# Flatsat_Connectors.net
KiCad netlist of a schematic drawn in Altium Designer
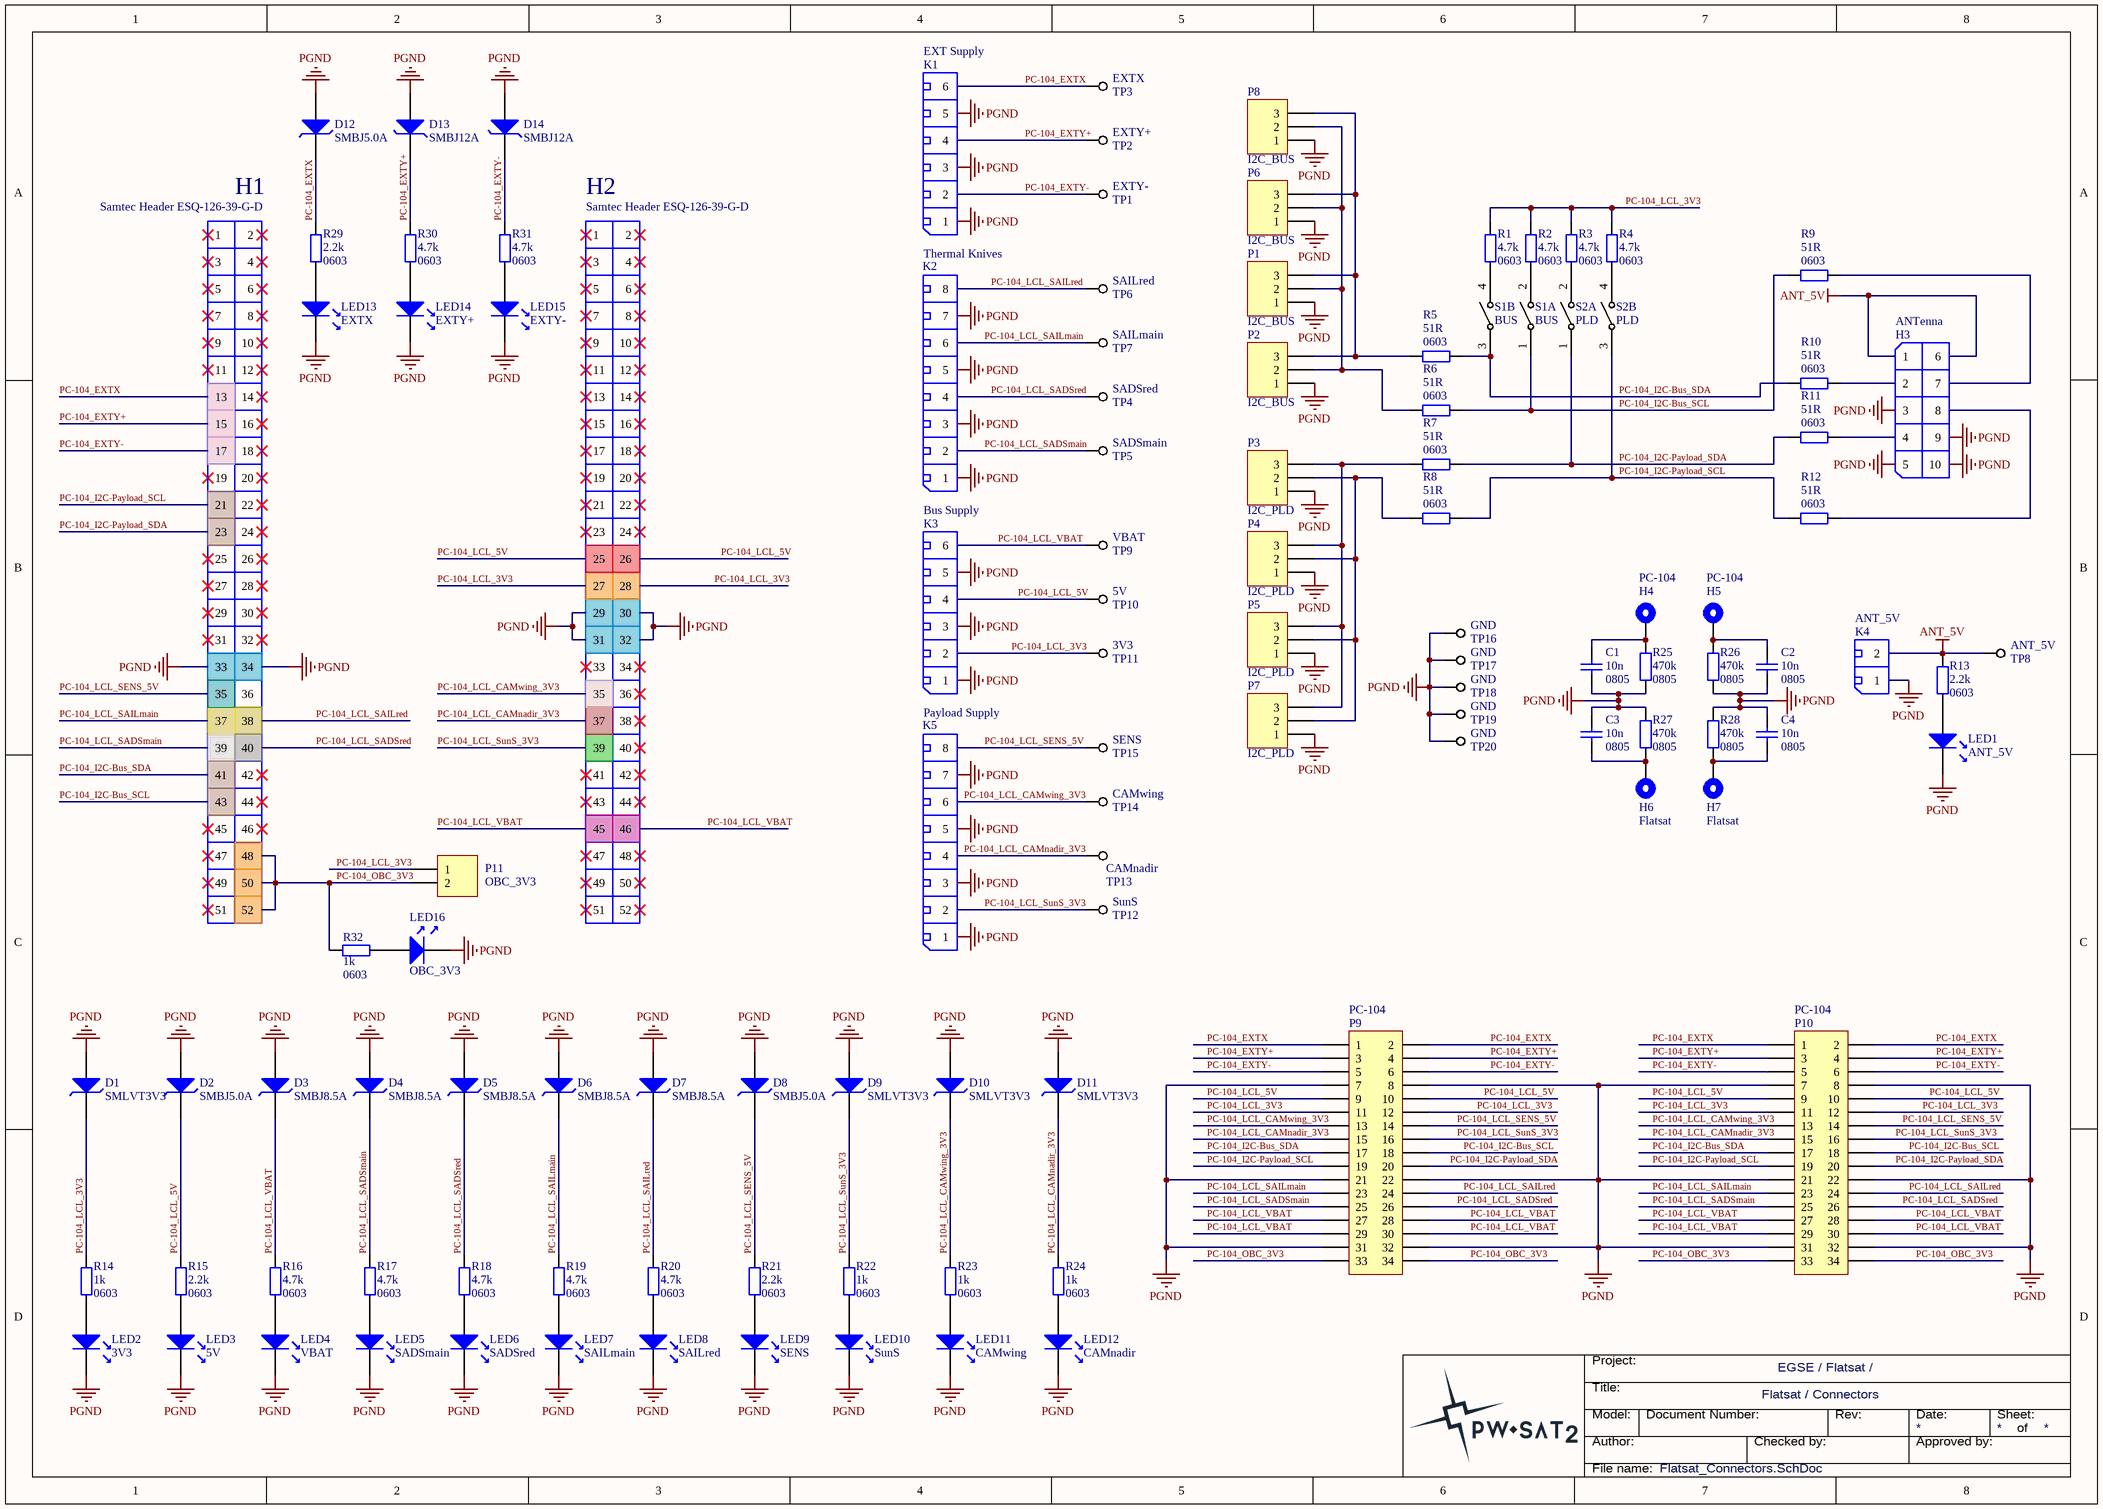
[diagram p0: Flatsat_Connectors.SchDoc]

(export (version "E")
  (design (tool "Eeschema 10.0.6"))
  (components
    (comp (ref "C1")
      (value "10n")
      (footprint "SMD_Capacitor_0805")
      (description "Cap")
      (fields (field (name "PACKAGE") "0805"))
      (libsource (lib "capacitors") (part "Cap"))
    )
    (comp (ref "C2")
      (value "10n")
      (footprint "SMD_Capacitor_0805")
      (description "Cap")
      (fields (field (name "PACKAGE") "0805"))
      (libsource (lib "capacitors") (part "Cap"))
    )
    (comp (ref "C3")
      (value "10n")
      (footprint "SMD_Capacitor_0805")
      (description "Cap")
      (fields (field (name "PACKAGE") "0805"))
      (libsource (lib "capacitors") (part "Cap"))
    )
    (comp (ref "C4")
      (value "10n")
      (footprint "SMD_Capacitor_0805")
      (description "Cap")
      (fields (field (name "PACKAGE") "0805"))
      (libsource (lib "capacitors") (part "Cap"))
    )
    (comp (ref "D1")
      (value "SMLVT3V3")
      (footprint "DO-214AA")
      (description "Low voltage Transil 3.3V")
      (fields (field (name "MANUFACTURER") "STMicroelectronics"))
      (libsource (lib "diodes") (part "SMLVT3V3"))
    )
    (comp (ref "D2")
      (value "SMBJ5.0A")
      (footprint "DO-214AA")
      (description "Transil 5V")
      (fields (field (name "MANUFACTURER") "STMicroelectronics"))
      (libsource (lib "diodes") (part "SMBJ5.0A"))
    )
    (comp (ref "D3")
      (value "SMBJ8.5A")
      (footprint "DO-214AA")
      (description "Transient Voltage Suppression Diodes 8.5V")
      (fields (field (name "MANUFACTURER") "Littelfuse"))
      (libsource (lib "diodes") (part "SMBJ8.5A"))
    )
    (comp (ref "D4")
      (value "SMBJ8.5A")
      (footprint "DO-214AA")
      (description "Transient Voltage Suppression Diodes 8.5V")
      (fields (field (name "MANUFACTURER") "Littelfuse"))
      (libsource (lib "diodes") (part "SMBJ8.5A"))
    )
    (comp (ref "D5")
      (value "SMBJ8.5A")
      (footprint "DO-214AA")
      (description "Transient Voltage Suppression Diodes 8.5V")
      (fields (field (name "MANUFACTURER") "Littelfuse"))
      (libsource (lib "diodes") (part "SMBJ8.5A"))
    )
    (comp (ref "D6")
      (value "SMBJ8.5A")
      (footprint "DO-214AA")
      (description "Transient Voltage Suppression Diodes 8.5V")
      (fields (field (name "MANUFACTURER") "Littelfuse"))
      (libsource (lib "diodes") (part "SMBJ8.5A"))
    )
    (comp (ref "D7")
      (value "SMBJ8.5A")
      (footprint "DO-214AA")
      (description "Transient Voltage Suppression Diodes 8.5V")
      (fields (field (name "MANUFACTURER") "Littelfuse"))
      (libsource (lib "diodes") (part "SMBJ8.5A"))
    )
    (comp (ref "D8")
      (value "SMBJ5.0A")
      (footprint "DO-214AA")
      (description "Transil 5V")
      (fields (field (name "MANUFACTURER") "STMicroelectronics"))
      (libsource (lib "diodes") (part "SMBJ5.0A"))
    )
    (comp (ref "D9")
      (value "SMLVT3V3")
      (footprint "DO-214AA")
      (description "Low voltage Transil 3.3V")
      (fields (field (name "MANUFACTURER") "STMicroelectronics"))
      (libsource (lib "diodes") (part "SMLVT3V3"))
    )
    (comp (ref "D10")
      (value "SMLVT3V3")
      (footprint "DO-214AA")
      (description "Low voltage Transil 3.3V")
      (fields (field (name "MANUFACTURER") "STMicroelectronics"))
      (libsource (lib "diodes") (part "SMLVT3V3"))
    )
    (comp (ref "D11")
      (value "SMLVT3V3")
      (footprint "DO-214AA")
      (description "Low voltage Transil 3.3V")
      (fields (field (name "MANUFACTURER") "STMicroelectronics"))
      (libsource (lib "diodes") (part "SMLVT3V3"))
    )
    (comp (ref "D12")
      (value "SMBJ5.0A")
      (footprint "DO-214AA")
      (description "Transil 5V")
      (fields (field (name "MANUFACTURER") "STMicroelectronics"))
      (libsource (lib "diodes") (part "SMBJ5.0A"))
    )
    (comp (ref "D13")
      (value "SMBJ12A")
      (footprint "DO-214AA")
      (description "Transil 12V")
      (fields (field (name "MANUFACTURER") "Littelfuse"))
      (libsource (lib "diodes") (part "SMBJ12A"))
    )
    (comp (ref "D14")
      (value "SMBJ12A")
      (footprint "DO-214AA")
      (description "Transil 12V")
      (fields (field (name "MANUFACTURER") "Littelfuse"))
      (libsource (lib "diodes") (part "SMBJ12A"))
    )
    (comp (ref "H1")
      (value "Samtec Header ESQ-126-39-G-D")
      (footprint "Samtec_ESQ-126-39-G-D")
      (description "Samtec ESQ Series Header , 2.54mm pitch, 2x26pin. PC-104 Stack Connector.")
      (libsource (lib "connectors_printed-circuit-board") (part "Samtec_ESQ-126-xx-x-D"))
    )
    (comp (ref "H2")
      (value "Samtec Header ESQ-126-39-G-D")
      (footprint "Samtec_ESQ-126-39-G-D")
      (description "Samtec ESQ Series Header , 2.54mm pitch, 2x26pin. PC-104 Stack Connector.")
      (libsource (lib "connectors_printed-circuit-board") (part "Samtec_ESQ-126-xx-x-D"))
    )
    (comp (ref "H3")
      (value "ANTenna")
      (footprint "Harwin_Datamate_L-Tek_M80-8671005")
      (description "Harwin DataMate L-Tek, 2mm pitch, 2x5pin.")
      (libsource (lib "connectors_printed-circuit-board") (part "Harwin_Datamate_L-Tek_2x5pin"))
    )
    (comp (ref "H4")
      (value "PC-104")
      (footprint "PC-104_PcbMntHole_M3")
      (description "PCB Mounting Hole")
      (libsource (lib "connectors_printed-circuit-board") (part "MntHole"))
    )
    (comp (ref "H5")
      (value "PC-104")
      (footprint "PC-104_PcbMntHole_M3")
      (description "PCB Mounting Hole")
      (libsource (lib "connectors_printed-circuit-board") (part "MntHole"))
    )
    (comp (ref "H6")
      (value "Flatsat")
      (footprint "PC-104_PcbMntHole_M3")
      (description "PCB Mounting Hole")
      (libsource (lib "connectors_printed-circuit-board") (part "MntHole"))
    )
    (comp (ref "H7")
      (value "Flatsat")
      (footprint "PC-104_PcbMntHole_M3")
      (description "PCB Mounting Hole")
      (libsource (lib "connectors_printed-circuit-board") (part "MntHole"))
    )
    (comp (ref "K1")
      (value "EXT Supply")
      (footprint "TerminalBlock_Spring_2.54_6-R")
      (description "Terminal block with spring, 6-pin, 2.54mm pitch, right angle.")
      (fields (field (name "PROVIDERPARTNUMBER") "TB-2.5-PD-xx") (field (name "PROVIDER") "TME.eu"))
      (libsource (lib "connectors_printed-circuit-board") (part "TerminalBlock_Spring_2.54_6-R"))
    )
    (comp (ref "K2")
      (value "Thermal Knives")
      (footprint "TerminalBlock_Spring_2.54_8-R")
      (description "Terminal block with spring, 8-pin, 2.54mm pitch, right angle.")
      (fields (field (name "PROVIDERPARTNUMBER") "TB-2.5-PD-xx") (field (name "PROVIDER") "TME.eu"))
      (libsource (lib "connectors_printed-circuit-board") (part "TerminalBlock_Spring_2.54_8-R"))
    )
    (comp (ref "K3")
      (value "Bus Supply")
      (footprint "TerminalBlock_Spring_2.54_6-R")
      (description "Terminal block with spring, 6-pin, 2.54mm pitch, right angle.")
      (fields (field (name "PROVIDERPARTNUMBER") "TB-2.5-PD-xx") (field (name "PROVIDER") "TME.eu"))
      (libsource (lib "connectors_printed-circuit-board") (part "TerminalBlock_Spring_2.54_6-R"))
    )
    (comp (ref "K4")
      (value "ANT_5V")
      (footprint "TerminalBlock_Spring_2.54_2-R")
      (description "Terminal block with spring, 2-pin, 2.54mm pitch, right angle.")
      (fields (field (name "PROVIDERPARTNUMBER") "TB-2.5-PD-xx") (field (name "PROVIDER") "TME.eu"))
      (libsource (lib "connectors_printed-circuit-board") (part "TerminalBlock_Spring_2.54_2-R"))
    )
    (comp (ref "K5")
      (value "Payload Supply")
      (footprint "TerminalBlock_Spring_2.54_8-R")
      (description "Terminal block with spring, 8-pin, 2.54mm pitch, right angle.")
      (fields (field (name "PROVIDERPARTNUMBER") "TB-2.5-PD-xx") (field (name "PROVIDER") "TME.eu"))
      (libsource (lib "connectors_printed-circuit-board") (part "TerminalBlock_Spring_2.54_8-R"))
    )
    (comp (ref "LED1")
      (value "ANT_5V")
      (footprint "SMD_LED_1206")
      (description "LED diode, SMD1206 package.")
      (libsource (lib "diodes") (part "LED-1206_RED"))
    )
    (comp (ref "LED2")
      (value "3V3")
      (footprint "SMD_LED_1206")
      (description "LED diode, SMD1206 package.")
      (libsource (lib "diodes") (part "LED-1206_RED"))
    )
    (comp (ref "LED3")
      (value "5V")
      (footprint "SMD_LED_1206")
      (description "LED diode, SMD1206 package.")
      (libsource (lib "diodes") (part "LED-1206_RED"))
    )
    (comp (ref "LED4")
      (value "VBAT")
      (footprint "SMD_LED_1206")
      (description "LED diode, SMD1206 package.")
      (libsource (lib "diodes") (part "LED-1206_RED"))
    )
    (comp (ref "LED5")
      (value "SADSmain")
      (footprint "SMD_LED_1206")
      (description "LED diode, SMD1206 package.")
      (libsource (lib "diodes") (part "LED-1206_RED"))
    )
    (comp (ref "LED6")
      (value "SADSred")
      (footprint "SMD_LED_1206")
      (description "LED diode, SMD1206 package.")
      (libsource (lib "diodes") (part "LED-1206_RED"))
    )
    (comp (ref "LED7")
      (value "SAILmain")
      (footprint "SMD_LED_1206")
      (description "LED diode, SMD1206 package.")
      (libsource (lib "diodes") (part "LED-1206_RED"))
    )
    (comp (ref "LED8")
      (value "SAILred")
      (footprint "SMD_LED_1206")
      (description "LED diode, SMD1206 package.")
      (libsource (lib "diodes") (part "LED-1206_RED"))
    )
    (comp (ref "LED9")
      (value "SENS")
      (footprint "SMD_LED_1206")
      (description "LED diode, SMD1206 package.")
      (libsource (lib "diodes") (part "LED-1206_RED"))
    )
    (comp (ref "LED10")
      (value "SunS")
      (footprint "SMD_LED_1206")
      (description "LED diode, SMD1206 package.")
      (libsource (lib "diodes") (part "LED-1206_RED"))
    )
    (comp (ref "LED11")
      (value "CAMwing")
      (footprint "SMD_LED_1206")
      (description "LED diode, SMD1206 package.")
      (libsource (lib "diodes") (part "LED-1206_RED"))
    )
    (comp (ref "LED12")
      (value "CAMnadir")
      (footprint "SMD_LED_1206")
      (description "LED diode, SMD1206 package.")
      (libsource (lib "diodes") (part "LED-1206_RED"))
    )
    (comp (ref "LED13")
      (value "EXTX")
      (footprint "SMD_LED_1206")
      (description "LED diode, SMD1206 package.")
      (libsource (lib "diodes") (part "LED-1206_RED"))
    )
    (comp (ref "LED14")
      (value "EXTY+")
      (footprint "SMD_LED_1206")
      (description "LED diode, SMD1206 package.")
      (libsource (lib "diodes") (part "LED-1206_RED"))
    )
    (comp (ref "LED15")
      (value "EXTY-")
      (footprint "SMD_LED_1206")
      (description "LED diode, SMD1206 package.")
      (libsource (lib "diodes") (part "LED-1206_RED"))
    )
    (comp (ref "LED16")
      (value "OBC_3V3")
      (footprint "SMD_LED_1206")
      (description "LED diode, SMD1206 package.")
      (libsource (lib "diodes") (part "LED-1206_RED"))
    )
    (comp (ref "P1")
      (value "I2C_BUS")
      (footprint "HEADER 1X3 MALE")
      (description "Header, 3-Pin")
      (fields (field (name "PUBLISHER") "Altium Limited"))
      (libsource (lib "connectors_printed-circuit-board") (part "Header 3"))
    )
    (comp (ref "P2")
      (value "I2C_BUS")
      (footprint "HEADER 1X3 MALE")
      (description "Header, 3-Pin")
      (fields (field (name "PUBLISHER") "Altium Limited"))
      (libsource (lib "connectors_printed-circuit-board") (part "Header 3"))
    )
    (comp (ref "P3")
      (value "I2C_PLD")
      (footprint "HEADER 1X3 MALE")
      (description "Header, 3-Pin")
      (fields (field (name "PUBLISHER") "Altium Limited"))
      (libsource (lib "connectors_printed-circuit-board") (part "Header 3"))
    )
    (comp (ref "P4")
      (value "I2C_PLD")
      (footprint "HEADER 1X3 MALE")
      (description "Header, 3-Pin")
      (fields (field (name "PUBLISHER") "Altium Limited"))
      (libsource (lib "connectors_printed-circuit-board") (part "Header 3"))
    )
    (comp (ref "P5")
      (value "I2C_PLD")
      (footprint "HEADER 1X3 MALE")
      (description "Header, 3-Pin")
      (fields (field (name "PUBLISHER") "Altium Limited"))
      (libsource (lib "connectors_printed-circuit-board") (part "Header 3"))
    )
    (comp (ref "P6")
      (value "I2C_BUS")
      (footprint "HEADER 1X3 MALE")
      (description "Header, 3-Pin")
      (fields (field (name "PUBLISHER") "Altium Limited"))
      (libsource (lib "connectors_printed-circuit-board") (part "Header 3"))
    )
    (comp (ref "P7")
      (value "I2C_PLD")
      (footprint "HEADER 1X3 MALE")
      (description "Header, 3-Pin")
      (fields (field (name "PUBLISHER") "Altium Limited"))
      (libsource (lib "connectors_printed-circuit-board") (part "Header 3"))
    )
    (comp (ref "P8")
      (value "I2C_BUS")
      (footprint "HEADER 1X3 MALE")
      (description "Header, 3-Pin")
      (fields (field (name "PUBLISHER") "Altium Limited"))
      (libsource (lib "connectors_printed-circuit-board") (part "Header 3"))
    )
    (comp (ref "P9")
      (value "PC-104")
      (footprint "IDC-34-Male-Socket")
      (description "Header, 17-Pin, Dual row")
      (fields (field (name "PUBLISHER") "Altium Limited"))
      (libsource (lib "connectors_printed-circuit-board") (part "Header 17X2"))
    )
    (comp (ref "P10")
      (value "PC-104")
      (footprint "IDC-34-Male-Socket")
      (description "Header, 17-Pin, Dual row")
      (fields (field (name "PUBLISHER") "Altium Limited"))
      (libsource (lib "connectors_printed-circuit-board") (part "Header 17X2"))
    )
    (comp (ref "P11")
      (value "OBC_3V3")
      (footprint "HEADER 1X2 Male")
      (description "Header, 2-Pin")
      (fields (field (name "PUBLISHER") "Altium Limited"))
      (libsource (lib "connectors_printed-circuit-board") (part "Header 2"))
    )
    (comp (ref "R1")
      (value "4.7k")
      (footprint "SMD_Resistor_0603")
      (fields (field (name "PACKAGE") "0603"))
      (libsource (lib "resistors") (part "Res"))
    )
    (comp (ref "R2")
      (value "4.7k")
      (footprint "SMD_Resistor_0603")
      (fields (field (name "PACKAGE") "0603"))
      (libsource (lib "resistors") (part "Res"))
    )
    (comp (ref "R3")
      (value "4.7k")
      (footprint "SMD_Resistor_0603")
      (fields (field (name "PACKAGE") "0603"))
      (libsource (lib "resistors") (part "Res"))
    )
    (comp (ref "R4")
      (value "4.7k")
      (footprint "SMD_Resistor_0603")
      (fields (field (name "PACKAGE") "0603"))
      (libsource (lib "resistors") (part "Res"))
    )
    (comp (ref "R5")
      (value "51R")
      (footprint "SMD_Resistor_0603")
      (fields (field (name "PACKAGE") "0603"))
      (libsource (lib "") (part "Res_1"))
    )
    (comp (ref "R6")
      (value "51R")
      (footprint "SMD_Resistor_0603")
      (fields (field (name "PACKAGE") "0603"))
      (libsource (lib "") (part "Res_1"))
    )
    (comp (ref "R7")
      (value "51R")
      (footprint "SMD_Resistor_0603")
      (fields (field (name "PACKAGE") "0603"))
      (libsource (lib "") (part "Res_1"))
    )
    (comp (ref "R8")
      (value "51R")
      (footprint "SMD_Resistor_0603")
      (fields (field (name "PACKAGE") "0603"))
      (libsource (lib "") (part "Res_1"))
    )
    (comp (ref "R9")
      (value "51R")
      (footprint "SMD_Resistor_0603")
      (fields (field (name "PACKAGE") "0603"))
      (libsource (lib "") (part "Res_1"))
    )
    (comp (ref "R10")
      (value "51R")
      (footprint "SMD_Resistor_0603")
      (fields (field (name "PACKAGE") "0603"))
      (libsource (lib "") (part "Res_1"))
    )
    (comp (ref "R11")
      (value "51R")
      (footprint "SMD_Resistor_0603")
      (fields (field (name "PACKAGE") "0603"))
      (libsource (lib "") (part "Res_1"))
    )
    (comp (ref "R12")
      (value "51R")
      (footprint "SMD_Resistor_0603")
      (fields (field (name "PACKAGE") "0603"))
      (libsource (lib "") (part "Res_1"))
    )
    (comp (ref "R13")
      (value "2.2k")
      (footprint "SMD_Resistor_0603")
      (fields (field (name "PACKAGE") "0603"))
      (libsource (lib "resistors") (part "Res"))
    )
    (comp (ref "R14")
      (value "1k")
      (footprint "SMD_Resistor_0603")
      (fields (field (name "PACKAGE") "0603"))
      (libsource (lib "resistors") (part "Res"))
    )
    (comp (ref "R15")
      (value "2.2k")
      (footprint "SMD_Resistor_0603")
      (fields (field (name "PACKAGE") "0603"))
      (libsource (lib "resistors") (part "Res"))
    )
    (comp (ref "R16")
      (value "4.7k")
      (footprint "SMD_Resistor_0603")
      (fields (field (name "PACKAGE") "0603"))
      (libsource (lib "resistors") (part "Res"))
    )
    (comp (ref "R17")
      (value "4.7k")
      (footprint "SMD_Resistor_0603")
      (fields (field (name "PACKAGE") "0603"))
      (libsource (lib "resistors") (part "Res"))
    )
    (comp (ref "R18")
      (value "4.7k")
      (footprint "SMD_Resistor_0603")
      (fields (field (name "PACKAGE") "0603"))
      (libsource (lib "resistors") (part "Res"))
    )
    (comp (ref "R19")
      (value "4.7k")
      (footprint "SMD_Resistor_0603")
      (fields (field (name "PACKAGE") "0603"))
      (libsource (lib "resistors") (part "Res"))
    )
    (comp (ref "R20")
      (value "4.7k")
      (footprint "SMD_Resistor_0603")
      (fields (field (name "PACKAGE") "0603"))
      (libsource (lib "resistors") (part "Res"))
    )
    (comp (ref "R21")
      (value "2.2k")
      (footprint "SMD_Resistor_0603")
      (fields (field (name "PACKAGE") "0603"))
      (libsource (lib "resistors") (part "Res"))
    )
    (comp (ref "R22")
      (value "1k")
      (footprint "SMD_Resistor_0603")
      (fields (field (name "PACKAGE") "0603"))
      (libsource (lib "resistors") (part "Res"))
    )
    (comp (ref "R23")
      (value "1k")
      (footprint "SMD_Resistor_0603")
      (fields (field (name "PACKAGE") "0603"))
      (libsource (lib "resistors") (part "Res"))
    )
    (comp (ref "R24")
      (value "1k")
      (footprint "SMD_Resistor_0603")
      (fields (field (name "PACKAGE") "0603"))
      (libsource (lib "resistors") (part "Res"))
    )
    (comp (ref "R25")
      (value "470k")
      (footprint "SMD_Resistor_0805")
      (fields (field (name "PACKAGE") "0805"))
      (libsource (lib "resistors") (part "Res"))
    )
    (comp (ref "R26")
      (value "470k")
      (footprint "SMD_Resistor_0805")
      (fields (field (name "PACKAGE") "0805"))
      (libsource (lib "resistors") (part "Res"))
    )
    (comp (ref "R27")
      (value "470k")
      (footprint "SMD_Resistor_0805")
      (fields (field (name "PACKAGE") "0805"))
      (libsource (lib "") (part "Res_1"))
    )
    (comp (ref "R28")
      (value "470k")
      (footprint "SMD_Resistor_0805")
      (fields (field (name "PACKAGE") "0805"))
      (libsource (lib "") (part "Res_1"))
    )
    (comp (ref "R29")
      (value "2.2k")
      (footprint "SMD_Resistor_0603")
      (fields (field (name "PACKAGE") "0603"))
      (libsource (lib "resistors") (part "Res"))
    )
    (comp (ref "R30")
      (value "4.7k")
      (footprint "SMD_Resistor_0603")
      (fields (field (name "PACKAGE") "0603"))
      (libsource (lib "resistors") (part "Res"))
    )
    (comp (ref "R31")
      (value "4.7k")
      (footprint "SMD_Resistor_0603")
      (fields (field (name "PACKAGE") "0603"))
      (libsource (lib "resistors") (part "Res"))
    )
    (comp (ref "R32")
      (value "1k")
      (footprint "SMD_Resistor_0603")
      (fields (field (name "PACKAGE") "0603"))
      (libsource (lib "") (part "Res_1"))
    )
    (comp (ref "S1") (value "BUS") (footprint "MCEPM-02") (libsource (lib "") (part "MCEPM-02_1")))
    (comp (ref "S2") (value "PLD") (footprint "MCEPM-02") (libsource (lib "switches") (part "MCEPM-02")))
    (comp (ref "TP1")
      (value "EXTY-")
      (footprint "Testpoint-1pin")
      (description "Testpoint")
      (libsource (lib "connectors_printed-circuit-board") (part "Testpoint"))
    )
    (comp (ref "TP2")
      (value "EXTY+")
      (footprint "Testpoint-1pin")
      (description "Testpoint")
      (libsource (lib "connectors_printed-circuit-board") (part "Testpoint"))
    )
    (comp (ref "TP3")
      (value "EXTX")
      (footprint "Testpoint-1pin")
      (description "Testpoint")
      (libsource (lib "connectors_printed-circuit-board") (part "Testpoint"))
    )
    (comp (ref "TP4")
      (value "SADSred")
      (footprint "Testpoint-1pin")
      (description "Testpoint")
      (libsource (lib "connectors_printed-circuit-board") (part "Testpoint"))
    )
    (comp (ref "TP5")
      (value "SADSmain")
      (footprint "Testpoint-1pin")
      (description "Testpoint")
      (libsource (lib "connectors_printed-circuit-board") (part "Testpoint"))
    )
    (comp (ref "TP6")
      (value "SAILred")
      (footprint "Testpoint-1pin")
      (description "Testpoint")
      (libsource (lib "connectors_printed-circuit-board") (part "Testpoint"))
    )
    (comp (ref "TP7")
      (value "SAILmain")
      (footprint "Testpoint-1pin")
      (description "Testpoint")
      (libsource (lib "connectors_printed-circuit-board") (part "Testpoint"))
    )
    (comp (ref "TP8")
      (value "ANT_5V")
      (footprint "Testpoint-1pin")
      (description "Testpoint")
      (libsource (lib "connectors_printed-circuit-board") (part "Testpoint"))
    )
    (comp (ref "TP9")
      (value "VBAT")
      (footprint "Testpoint-1pin")
      (description "Testpoint")
      (libsource (lib "connectors_printed-circuit-board") (part "Testpoint"))
    )
    (comp (ref "TP10")
      (value "5V")
      (footprint "Testpoint-1pin")
      (description "Testpoint")
      (libsource (lib "connectors_printed-circuit-board") (part "Testpoint"))
    )
    (comp (ref "TP11")
      (value "3V3")
      (footprint "Testpoint-1pin")
      (description "Testpoint")
      (libsource (lib "connectors_printed-circuit-board") (part "Testpoint"))
    )
    (comp (ref "TP12")
      (value "SunS")
      (footprint "Testpoint-1pin")
      (description "Testpoint")
      (libsource (lib "connectors_printed-circuit-board") (part "Testpoint"))
    )
    (comp (ref "TP13")
      (value "CAMnadir")
      (footprint "Testpoint-1pin")
      (description "Testpoint")
      (libsource (lib "connectors_printed-circuit-board") (part "Testpoint"))
    )
    (comp (ref "TP14")
      (value "CAMwing")
      (footprint "Testpoint-1pin")
      (description "Testpoint")
      (libsource (lib "connectors_printed-circuit-board") (part "Testpoint"))
    )
    (comp (ref "TP15")
      (value "SENS")
      (footprint "Testpoint-1pin")
      (description "Testpoint")
      (libsource (lib "connectors_printed-circuit-board") (part "Testpoint"))
    )
    (comp (ref "TP16")
      (value "GND")
      (footprint "Testpoint-1pin")
      (description "Testpoint")
      (libsource (lib "connectors_printed-circuit-board") (part "Testpoint"))
    )
    (comp (ref "TP17")
      (value "GND")
      (footprint "Testpoint-1pin")
      (description "Testpoint")
      (libsource (lib "connectors_printed-circuit-board") (part "Testpoint"))
    )
    (comp (ref "TP18")
      (value "GND")
      (footprint "Testpoint-1pin")
      (description "Testpoint")
      (libsource (lib "connectors_printed-circuit-board") (part "Testpoint"))
    )
    (comp (ref "TP19")
      (value "GND")
      (footprint "Testpoint-1pin")
      (description "Testpoint")
      (libsource (lib "connectors_printed-circuit-board") (part "Testpoint"))
    )
    (comp (ref "TP20")
      (value "GND")
      (footprint "Testpoint-1pin")
      (description "Testpoint")
      (libsource (lib "connectors_printed-circuit-board") (part "Testpoint"))
    )
  )
  (nets
    (net (code "1") (name "/PC-104_EXTX") (class "Default")
      (node (ref "D12") (pin "K") (pinfunction "K_K") (pintype "passive"))
      (node (ref "H1") (pin "13") (pinfunction "13_13") (pintype "passive"))
      (node (ref "K1") (pin "6") (pinfunction "6_6") (pintype "passive"))
      (node (ref "P10") (pin "1") (pinfunction "1_1") (pintype "passive"))
      (node (ref "P10") (pin "2") (pinfunction "2_2") (pintype "passive"))
      (node (ref "P9") (pin "1") (pinfunction "1_1") (pintype "passive"))
      (node (ref "P9") (pin "2") (pinfunction "2_2") (pintype "passive"))
      (node (ref "R29") (pin "1") (pinfunction "1_1") (pintype "passive"))
      (node (ref "TP3") (pin "1") (pinfunction "TP_1") (pintype "passive"))
    )
    (net (code "2") (name "/PC-104_EXTY+") (class "Default")
      (node (ref "D13") (pin "K") (pinfunction "K_K") (pintype "passive"))
      (node (ref "H1") (pin "15") (pinfunction "15_15") (pintype "passive"))
      (node (ref "K1") (pin "4") (pinfunction "4_4") (pintype "passive"))
      (node (ref "P10") (pin "3") (pinfunction "3_3") (pintype "passive"))
      (node (ref "P10") (pin "4") (pinfunction "4_4") (pintype "passive"))
      (node (ref "P9") (pin "3") (pinfunction "3_3") (pintype "passive"))
      (node (ref "P9") (pin "4") (pinfunction "4_4") (pintype "passive"))
      (node (ref "R30") (pin "1") (pinfunction "1_1") (pintype "passive"))
      (node (ref "TP2") (pin "1") (pinfunction "TP_1") (pintype "passive"))
    )
    (net (code "3") (name "/PC-104_EXTY-") (class "Default")
      (node (ref "D14") (pin "K") (pinfunction "K_K") (pintype "passive"))
      (node (ref "H1") (pin "17") (pinfunction "17_17") (pintype "passive"))
      (node (ref "K1") (pin "2") (pinfunction "2_2") (pintype "passive"))
      (node (ref "P10") (pin "5") (pinfunction "5_5") (pintype "passive"))
      (node (ref "P10") (pin "6") (pinfunction "6_6") (pintype "passive"))
      (node (ref "P9") (pin "5") (pinfunction "5_5") (pintype "passive"))
      (node (ref "P9") (pin "6") (pinfunction "6_6") (pintype "passive"))
      (node (ref "R31") (pin "1") (pinfunction "1_1") (pintype "passive"))
      (node (ref "TP1") (pin "1") (pinfunction "TP_1") (pintype "passive"))
    )
    (net (code "4") (name "/PC-104_I2C-Bus_SCL") (class "Default")
      (node (ref "H1") (pin "43") (pinfunction "43_43") (pintype "passive"))
      (node (ref "P10") (pin "18") (pinfunction "18_18") (pintype "passive"))
      (node (ref "P9") (pin "18") (pinfunction "18_18") (pintype "passive"))
      (node (ref "R6") (pin "2") (pinfunction "2_2") (pintype "passive"))
      (node (ref "R9") (pin "1") (pinfunction "1_1") (pintype "passive"))
      (node (ref "S1") (pin "1") (pinfunction "1_1") (pintype "passive"))
    )
    (net (code "5") (name "/PC-104_I2C-Bus_SDA") (class "Default")
      (node (ref "H1") (pin "41") (pinfunction "41_41") (pintype "passive"))
      (node (ref "P10") (pin "17") (pinfunction "17_17") (pintype "passive"))
      (node (ref "P9") (pin "17") (pinfunction "17_17") (pintype "passive"))
      (node (ref "R10") (pin "1") (pinfunction "1_1") (pintype "passive"))
      (node (ref "R5") (pin "2") (pinfunction "2_2") (pintype "passive"))
      (node (ref "S1") (pin "3") (pinfunction "3_3") (pintype "passive"))
    )
    (net (code "6") (name "/PC-104_I2C-Payload_SCL") (class "Default")
      (node (ref "H1") (pin "21") (pinfunction "21_21") (pintype "passive"))
      (node (ref "P10") (pin "19") (pinfunction "19_19") (pintype "passive"))
      (node (ref "P9") (pin "19") (pinfunction "19_19") (pintype "passive"))
      (node (ref "R12") (pin "1") (pinfunction "1_1") (pintype "passive"))
      (node (ref "R8") (pin "2") (pinfunction "2_2") (pintype "passive"))
      (node (ref "S2") (pin "3") (pinfunction "3_3") (pintype "passive"))
    )
    (net (code "7") (name "/PC-104_I2C-Payload_SDA") (class "Default")
      (node (ref "H1") (pin "23") (pinfunction "23_23") (pintype "passive"))
      (node (ref "P10") (pin "20") (pinfunction "20_20") (pintype "passive"))
      (node (ref "P9") (pin "20") (pinfunction "20_20") (pintype "passive"))
      (node (ref "R11") (pin "1") (pinfunction "1_1") (pintype "passive"))
      (node (ref "R7") (pin "2") (pinfunction "2_2") (pintype "passive"))
      (node (ref "S2") (pin "1") (pinfunction "1_1") (pintype "passive"))
    )
    (net (code "8") (name "/PC-104_LCL_3V3") (class "Default")
      (node (ref "D1") (pin "K") (pinfunction "K_K") (pintype "passive"))
      (node (ref "H2") (pin "27") (pinfunction "27_27") (pintype "passive"))
      (node (ref "H2") (pin "28") (pinfunction "28_28") (pintype "passive"))
      (node (ref "K3") (pin "2") (pinfunction "2_2") (pintype "passive"))
      (node (ref "P10") (pin "11") (pinfunction "11_11") (pintype "passive"))
      (node (ref "P10") (pin "12") (pinfunction "12_12") (pintype "passive"))
      (node (ref "P11") (pin "1") (pinfunction "1_1") (pintype "passive"))
      (node (ref "P9") (pin "11") (pinfunction "11_11") (pintype "passive"))
      (node (ref "P9") (pin "12") (pinfunction "12_12") (pintype "passive"))
      (node (ref "R1") (pin "1") (pinfunction "1_1") (pintype "passive"))
      (node (ref "R14") (pin "1") (pinfunction "1_1") (pintype "passive"))
      (node (ref "R2") (pin "1") (pinfunction "1_1") (pintype "passive"))
      (node (ref "R3") (pin "1") (pinfunction "1_1") (pintype "passive"))
      (node (ref "R4") (pin "1") (pinfunction "1_1") (pintype "passive"))
      (node (ref "TP11") (pin "1") (pinfunction "TP_1") (pintype "passive"))
    )
    (net (code "9") (name "/PC-104_LCL_5V") (class "Default")
      (node (ref "D2") (pin "K") (pinfunction "K_K") (pintype "passive"))
      (node (ref "H2") (pin "25") (pinfunction "25_25") (pintype "passive"))
      (node (ref "H2") (pin "26") (pinfunction "26_26") (pintype "passive"))
      (node (ref "K3") (pin "4") (pinfunction "4_4") (pintype "passive"))
      (node (ref "P10") (pin "10") (pinfunction "10_10") (pintype "passive"))
      (node (ref "P10") (pin "9") (pinfunction "9_9") (pintype "passive"))
      (node (ref "P9") (pin "10") (pinfunction "10_10") (pintype "passive"))
      (node (ref "P9") (pin "9") (pinfunction "9_9") (pintype "passive"))
      (node (ref "R15") (pin "1") (pinfunction "1_1") (pintype "passive"))
      (node (ref "TP10") (pin "1") (pinfunction "TP_1") (pintype "passive"))
    )
    (net (code "10") (name "/PC-104_LCL_CAMnadir_3V3") (class "Default")
      (node (ref "D11") (pin "K") (pinfunction "K_K") (pintype "passive"))
      (node (ref "H2") (pin "37") (pinfunction "37_37") (pintype "passive"))
      (node (ref "K5") (pin "4") (pinfunction "4_4") (pintype "passive"))
      (node (ref "P10") (pin "15") (pinfunction "15_15") (pintype "passive"))
      (node (ref "P9") (pin "15") (pinfunction "15_15") (pintype "passive"))
      (node (ref "R24") (pin "1") (pinfunction "1_1") (pintype "passive"))
      (node (ref "TP13") (pin "1") (pinfunction "TP_1") (pintype "passive"))
    )
    (net (code "11") (name "/PC-104_LCL_CAMwing_3V3") (class "Default")
      (node (ref "D10") (pin "K") (pinfunction "K_K") (pintype "passive"))
      (node (ref "H2") (pin "35") (pinfunction "35_35") (pintype "passive"))
      (node (ref "K5") (pin "6") (pinfunction "6_6") (pintype "passive"))
      (node (ref "P10") (pin "13") (pinfunction "13_13") (pintype "passive"))
      (node (ref "P9") (pin "13") (pinfunction "13_13") (pintype "passive"))
      (node (ref "R23") (pin "1") (pinfunction "1_1") (pintype "passive"))
      (node (ref "TP14") (pin "1") (pinfunction "TP_1") (pintype "passive"))
    )
    (net (code "12") (name "/PC-104_LCL_SADSmain") (class "Default")
      (node (ref "D4") (pin "K") (pinfunction "K_K") (pintype "passive"))
      (node (ref "H1") (pin "39") (pinfunction "39_39") (pintype "passive"))
      (node (ref "K2") (pin "2") (pinfunction "2_2") (pintype "passive"))
      (node (ref "P10") (pin "25") (pinfunction "25_25") (pintype "passive"))
      (node (ref "P9") (pin "25") (pinfunction "25_25") (pintype "passive"))
      (node (ref "R17") (pin "1") (pinfunction "1_1") (pintype "passive"))
      (node (ref "TP5") (pin "1") (pinfunction "TP_1") (pintype "passive"))
    )
    (net (code "13") (name "/PC-104_LCL_SADSred") (class "Default")
      (node (ref "D5") (pin "K") (pinfunction "K_K") (pintype "passive"))
      (node (ref "H1") (pin "40") (pinfunction "40_40") (pintype "passive"))
      (node (ref "K2") (pin "4") (pinfunction "4_4") (pintype "passive"))
      (node (ref "P10") (pin "26") (pinfunction "26_26") (pintype "passive"))
      (node (ref "P9") (pin "26") (pinfunction "26_26") (pintype "passive"))
      (node (ref "R18") (pin "1") (pinfunction "1_1") (pintype "passive"))
      (node (ref "TP4") (pin "1") (pinfunction "TP_1") (pintype "passive"))
    )
    (net (code "14") (name "/PC-104_LCL_SAILmain") (class "Default")
      (node (ref "D6") (pin "K") (pinfunction "K_K") (pintype "passive"))
      (node (ref "H1") (pin "37") (pinfunction "37_37") (pintype "passive"))
      (node (ref "K2") (pin "6") (pinfunction "6_6") (pintype "passive"))
      (node (ref "P10") (pin "23") (pinfunction "23_23") (pintype "passive"))
      (node (ref "P9") (pin "23") (pinfunction "23_23") (pintype "passive"))
      (node (ref "R19") (pin "1") (pinfunction "1_1") (pintype "passive"))
      (node (ref "TP7") (pin "1") (pinfunction "TP_1") (pintype "passive"))
    )
    (net (code "15") (name "/PC-104_LCL_SAILred") (class "Default")
      (node (ref "D7") (pin "K") (pinfunction "K_K") (pintype "passive"))
      (node (ref "H1") (pin "38") (pinfunction "38_38") (pintype "passive"))
      (node (ref "K2") (pin "8") (pinfunction "8_8") (pintype "passive"))
      (node (ref "P10") (pin "24") (pinfunction "24_24") (pintype "passive"))
      (node (ref "P9") (pin "24") (pinfunction "24_24") (pintype "passive"))
      (node (ref "R20") (pin "1") (pinfunction "1_1") (pintype "passive"))
      (node (ref "TP6") (pin "1") (pinfunction "TP_1") (pintype "passive"))
    )
    (net (code "16") (name "/PC-104_LCL_SENS_5V") (class "Default")
      (node (ref "D8") (pin "K") (pinfunction "K_K") (pintype "passive"))
      (node (ref "H1") (pin "35") (pinfunction "35_35") (pintype "passive"))
      (node (ref "K5") (pin "8") (pinfunction "8_8") (pintype "passive"))
      (node (ref "P10") (pin "14") (pinfunction "14_14") (pintype "passive"))
      (node (ref "P9") (pin "14") (pinfunction "14_14") (pintype "passive"))
      (node (ref "R21") (pin "1") (pinfunction "1_1") (pintype "passive"))
      (node (ref "TP15") (pin "1") (pinfunction "TP_1") (pintype "passive"))
    )
    (net (code "17") (name "/PC-104_LCL_SunS_3V3") (class "Default")
      (node (ref "D9") (pin "K") (pinfunction "K_K") (pintype "passive"))
      (node (ref "H2") (pin "39") (pinfunction "39_39") (pintype "passive"))
      (node (ref "K5") (pin "2") (pinfunction "2_2") (pintype "passive"))
      (node (ref "P10") (pin "16") (pinfunction "16_16") (pintype "passive"))
      (node (ref "P9") (pin "16") (pinfunction "16_16") (pintype "passive"))
      (node (ref "R22") (pin "1") (pinfunction "1_1") (pintype "passive"))
      (node (ref "TP12") (pin "1") (pinfunction "TP_1") (pintype "passive"))
    )
    (net (code "18") (name "/PC-104_LCL_VBAT") (class "Default")
      (node (ref "D3") (pin "K") (pinfunction "K_K") (pintype "passive"))
      (node (ref "H2") (pin "45") (pinfunction "45_45") (pintype "passive"))
      (node (ref "H2") (pin "46") (pinfunction "46_46") (pintype "passive"))
      (node (ref "K3") (pin "6") (pinfunction "6_6") (pintype "passive"))
      (node (ref "P10") (pin "27") (pinfunction "27_27") (pintype "passive"))
      (node (ref "P10") (pin "28") (pinfunction "28_28") (pintype "passive"))
      (node (ref "P10") (pin "29") (pinfunction "29_29") (pintype "passive"))
      (node (ref "P10") (pin "30") (pinfunction "30_30") (pintype "passive"))
      (node (ref "P9") (pin "27") (pinfunction "27_27") (pintype "passive"))
      (node (ref "P9") (pin "28") (pinfunction "28_28") (pintype "passive"))
      (node (ref "P9") (pin "29") (pinfunction "29_29") (pintype "passive"))
      (node (ref "P9") (pin "30") (pinfunction "30_30") (pintype "passive"))
      (node (ref "R16") (pin "1") (pinfunction "1_1") (pintype "passive"))
      (node (ref "TP9") (pin "1") (pinfunction "TP_1") (pintype "passive"))
    )
    (net (code "19") (name "/PC-104_OBC_3V3") (class "Default")
      (node (ref "H1") (pin "48") (pinfunction "48_48") (pintype "passive"))
      (node (ref "H1") (pin "50") (pinfunction "50_50") (pintype "passive"))
      (node (ref "H1") (pin "52") (pinfunction "52_52") (pintype "passive"))
      (node (ref "P10") (pin "33") (pinfunction "33_33") (pintype "passive"))
      (node (ref "P10") (pin "34") (pinfunction "34_34") (pintype "passive"))
      (node (ref "P11") (pin "2") (pinfunction "2_2") (pintype "passive"))
      (node (ref "P9") (pin "33") (pinfunction "33_33") (pintype "passive"))
      (node (ref "P9") (pin "34") (pinfunction "34_34") (pintype "passive"))
      (node (ref "R32") (pin "1") (pinfunction "1_1") (pintype "passive"))
    )
    (net (code "20") (name "ANT_5V") (class "Default")
      (node (ref "H3") (pin "1") (pinfunction "1_1") (pintype "passive"))
      (node (ref "H3") (pin "6") (pinfunction "6_6") (pintype "passive"))
      (node (ref "K4") (pin "2") (pinfunction "2_2") (pintype "passive"))
      (node (ref "R13") (pin "1") (pinfunction "1_1") (pintype "passive"))
      (node (ref "TP8") (pin "1") (pinfunction "TP_1") (pintype "passive"))
    )
    (net (code "21") (name "Net-(C1-Pad1)") (class "Default")
      (node (ref "C1") (pin "1") (pinfunction "1_1") (pintype "passive"))
      (node (ref "H4") (pin "1") (pinfunction "1_1") (pintype "passive"))
      (node (ref "R25") (pin "1") (pinfunction "1_1") (pintype "passive"))
    )
    (net (code "22") (name "Net-(C2-Pad1)") (class "Default")
      (node (ref "C2") (pin "1") (pinfunction "1_1") (pintype "passive"))
      (node (ref "H5") (pin "1") (pinfunction "1_1") (pintype "passive"))
      (node (ref "R26") (pin "1") (pinfunction "1_1") (pintype "passive"))
    )
    (net (code "23") (name "Net-(C3-Pad1)") (class "Default")
      (node (ref "C3") (pin "1") (pinfunction "1_1") (pintype "passive"))
      (node (ref "H6") (pin "1") (pinfunction "1_1") (pintype "passive"))
      (node (ref "R27") (pin "1") (pinfunction "1_1") (pintype "passive"))
    )
    (net (code "24") (name "Net-(C4-Pad1)") (class "Default")
      (node (ref "C4") (pin "1") (pinfunction "1_1") (pintype "passive"))
      (node (ref "H7") (pin "1") (pinfunction "1_1") (pintype "passive"))
      (node (ref "R28") (pin "1") (pinfunction "1_1") (pintype "passive"))
    )
    (net (code "25") (name "Net-(H3-Pad2)") (class "Default")
      (node (ref "H3") (pin "2") (pinfunction "2_2") (pintype "passive"))
      (node (ref "R10") (pin "2") (pinfunction "2_2") (pintype "passive"))
    )
    (net (code "26") (name "Net-(H3-Pad4)") (class "Default")
      (node (ref "H3") (pin "4") (pinfunction "4_4") (pintype "passive"))
      (node (ref "R11") (pin "2") (pinfunction "2_2") (pintype "passive"))
    )
    (net (code "27") (name "Net-(H3-Pad7)") (class "Default")
      (node (ref "H3") (pin "7") (pinfunction "7_7") (pintype "passive"))
      (node (ref "R9") (pin "2") (pinfunction "2_2") (pintype "passive"))
    )
    (net (code "28") (name "Net-(H3-Pad8)") (class "Default")
      (node (ref "H3") (pin "8") (pinfunction "8_8") (pintype "passive"))
      (node (ref "R12") (pin "2") (pinfunction "2_2") (pintype "passive"))
    )
    (net (code "29") (name "Net-(LED1-PadA)") (class "Default")
      (node (ref "LED1") (pin "A") (pinfunction "A_A") (pintype "passive"))
      (node (ref "R13") (pin "2") (pinfunction "2_2") (pintype "passive"))
    )
    (net (code "30") (name "Net-(LED2-PadA)") (class "Default")
      (node (ref "LED2") (pin "A") (pinfunction "A_A") (pintype "passive"))
      (node (ref "R14") (pin "2") (pinfunction "2_2") (pintype "passive"))
    )
    (net (code "31") (name "Net-(LED3-PadA)") (class "Default")
      (node (ref "LED3") (pin "A") (pinfunction "A_A") (pintype "passive"))
      (node (ref "R15") (pin "2") (pinfunction "2_2") (pintype "passive"))
    )
    (net (code "32") (name "Net-(LED4-PadA)") (class "Default")
      (node (ref "LED4") (pin "A") (pinfunction "A_A") (pintype "passive"))
      (node (ref "R16") (pin "2") (pinfunction "2_2") (pintype "passive"))
    )
    (net (code "33") (name "Net-(LED5-PadA)") (class "Default")
      (node (ref "LED5") (pin "A") (pinfunction "A_A") (pintype "passive"))
      (node (ref "R17") (pin "2") (pinfunction "2_2") (pintype "passive"))
    )
    (net (code "34") (name "Net-(LED6-PadA)") (class "Default")
      (node (ref "LED6") (pin "A") (pinfunction "A_A") (pintype "passive"))
      (node (ref "R18") (pin "2") (pinfunction "2_2") (pintype "passive"))
    )
    (net (code "35") (name "Net-(LED7-PadA)") (class "Default")
      (node (ref "LED7") (pin "A") (pinfunction "A_A") (pintype "passive"))
      (node (ref "R19") (pin "2") (pinfunction "2_2") (pintype "passive"))
    )
    (net (code "36") (name "Net-(LED8-PadA)") (class "Default")
      (node (ref "LED8") (pin "A") (pinfunction "A_A") (pintype "passive"))
      (node (ref "R20") (pin "2") (pinfunction "2_2") (pintype "passive"))
    )
    (net (code "37") (name "Net-(LED9-PadA)") (class "Default")
      (node (ref "LED9") (pin "A") (pinfunction "A_A") (pintype "passive"))
      (node (ref "R21") (pin "2") (pinfunction "2_2") (pintype "passive"))
    )
    (net (code "38") (name "Net-(LED10-PadA)") (class "Default")
      (node (ref "LED10") (pin "A") (pinfunction "A_A") (pintype "passive"))
      (node (ref "R22") (pin "2") (pinfunction "2_2") (pintype "passive"))
    )
    (net (code "39") (name "Net-(LED11-PadA)") (class "Default")
      (node (ref "LED11") (pin "A") (pinfunction "A_A") (pintype "passive"))
      (node (ref "R23") (pin "2") (pinfunction "2_2") (pintype "passive"))
    )
    (net (code "40") (name "Net-(LED12-PadA)") (class "Default")
      (node (ref "LED12") (pin "A") (pinfunction "A_A") (pintype "passive"))
      (node (ref "R24") (pin "2") (pinfunction "2_2") (pintype "passive"))
    )
    (net (code "41") (name "Net-(LED13-PadA)") (class "Default")
      (node (ref "LED13") (pin "A") (pinfunction "A_A") (pintype "passive"))
      (node (ref "R29") (pin "2") (pinfunction "2_2") (pintype "passive"))
    )
    (net (code "42") (name "Net-(LED14-PadA)") (class "Default")
      (node (ref "LED14") (pin "A") (pinfunction "A_A") (pintype "passive"))
      (node (ref "R30") (pin "2") (pinfunction "2_2") (pintype "passive"))
    )
    (net (code "43") (name "Net-(LED15-PadA)") (class "Default")
      (node (ref "LED15") (pin "A") (pinfunction "A_A") (pintype "passive"))
      (node (ref "R31") (pin "2") (pinfunction "2_2") (pintype "passive"))
    )
    (net (code "44") (name "Net-(LED16-PadA)") (class "Default")
      (node (ref "LED16") (pin "A") (pinfunction "A_A") (pintype "passive"))
      (node (ref "R32") (pin "2") (pinfunction "2_2") (pintype "passive"))
    )
    (net (code "45") (name "Net-(P1-Pad2)") (class "Default")
      (node (ref "P1") (pin "2") (pinfunction "2_2") (pintype "passive"))
      (node (ref "P2") (pin "2") (pinfunction "2_2") (pintype "passive"))
      (node (ref "P6") (pin "2") (pinfunction "2_2") (pintype "passive"))
      (node (ref "P8") (pin "2") (pinfunction "2_2") (pintype "passive"))
      (node (ref "R6") (pin "1") (pinfunction "1_1") (pintype "passive"))
    )
    (net (code "46") (name "Net-(P1-Pad3)") (class "Default")
      (node (ref "P1") (pin "3") (pinfunction "3_3") (pintype "passive"))
      (node (ref "P2") (pin "3") (pinfunction "3_3") (pintype "passive"))
      (node (ref "P6") (pin "3") (pinfunction "3_3") (pintype "passive"))
      (node (ref "P8") (pin "3") (pinfunction "3_3") (pintype "passive"))
      (node (ref "R5") (pin "1") (pinfunction "1_1") (pintype "passive"))
    )
    (net (code "47") (name "Net-(P3-Pad2)") (class "Default")
      (node (ref "P3") (pin "2") (pinfunction "2_2") (pintype "passive"))
      (node (ref "P4") (pin "2") (pinfunction "2_2") (pintype "passive"))
      (node (ref "P5") (pin "2") (pinfunction "2_2") (pintype "passive"))
      (node (ref "P7") (pin "2") (pinfunction "2_2") (pintype "passive"))
      (node (ref "R8") (pin "1") (pinfunction "1_1") (pintype "passive"))
    )
    (net (code "48") (name "Net-(P3-Pad3)") (class "Default")
      (node (ref "P3") (pin "3") (pinfunction "3_3") (pintype "passive"))
      (node (ref "P4") (pin "3") (pinfunction "3_3") (pintype "passive"))
      (node (ref "P5") (pin "3") (pinfunction "3_3") (pintype "passive"))
      (node (ref "P7") (pin "3") (pinfunction "3_3") (pintype "passive"))
      (node (ref "R7") (pin "1") (pinfunction "1_1") (pintype "passive"))
    )
    (net (code "49") (name "Net-(R1-Pad2)") (class "Default")
      (node (ref "R1") (pin "2") (pinfunction "2_2") (pintype "passive"))
      (node (ref "S1") (pin "4") (pinfunction "4_4") (pintype "passive"))
    )
    (net (code "50") (name "Net-(R2-Pad2)") (class "Default")
      (node (ref "R2") (pin "2") (pinfunction "2_2") (pintype "passive"))
      (node (ref "S1") (pin "2") (pinfunction "2_2") (pintype "passive"))
    )
    (net (code "51") (name "Net-(R3-Pad2)") (class "Default")
      (node (ref "R3") (pin "2") (pinfunction "2_2") (pintype "passive"))
      (node (ref "S2") (pin "2") (pinfunction "2_2") (pintype "passive"))
    )
    (net (code "52") (name "Net-(R4-Pad2)") (class "Default")
      (node (ref "R4") (pin "2") (pinfunction "2_2") (pintype "passive"))
      (node (ref "S2") (pin "4") (pinfunction "4_4") (pintype "passive"))
    )
    (net (code "53") (name "PGND") (class "Default")
      (node (ref "C1") (pin "2") (pinfunction "2_2") (pintype "passive"))
      (node (ref "C2") (pin "2") (pinfunction "2_2") (pintype "passive"))
      (node (ref "C3") (pin "2") (pinfunction "2_2") (pintype "passive"))
      (node (ref "C4") (pin "2") (pinfunction "2_2") (pintype "passive"))
      (node (ref "D1") (pin "A") (pinfunction "A_A") (pintype "passive"))
      (node (ref "D10") (pin "A") (pinfunction "A_A") (pintype "passive"))
      (node (ref "D11") (pin "A") (pinfunction "A_A") (pintype "passive"))
      (node (ref "D12") (pin "A") (pinfunction "A_A") (pintype "passive"))
      (node (ref "D13") (pin "A") (pinfunction "A_A") (pintype "passive"))
      (node (ref "D14") (pin "A") (pinfunction "A_A") (pintype "passive"))
      (node (ref "D2") (pin "A") (pinfunction "A_A") (pintype "passive"))
      (node (ref "D3") (pin "A") (pinfunction "A_A") (pintype "passive"))
      (node (ref "D4") (pin "A") (pinfunction "A_A") (pintype "passive"))
      (node (ref "D5") (pin "A") (pinfunction "A_A") (pintype "passive"))
      (node (ref "D6") (pin "A") (pinfunction "A_A") (pintype "passive"))
      (node (ref "D7") (pin "A") (pinfunction "A_A") (pintype "passive"))
      (node (ref "D8") (pin "A") (pinfunction "A_A") (pintype "passive"))
      (node (ref "D9") (pin "A") (pinfunction "A_A") (pintype "passive"))
      (node (ref "H1") (pin "33") (pinfunction "33_33") (pintype "passive"))
      (node (ref "H1") (pin "34") (pinfunction "34_34") (pintype "passive"))
      (node (ref "H2") (pin "29") (pinfunction "29_29") (pintype "passive"))
      (node (ref "H2") (pin "30") (pinfunction "30_30") (pintype "passive"))
      (node (ref "H2") (pin "31") (pinfunction "31_31") (pintype "passive"))
      (node (ref "H2") (pin "32") (pinfunction "32_32") (pintype "passive"))
      (node (ref "H3") (pin "10") (pinfunction "10_10") (pintype "passive"))
      (node (ref "H3") (pin "3") (pinfunction "3_3") (pintype "passive"))
      (node (ref "H3") (pin "5") (pinfunction "5_5") (pintype "passive"))
      (node (ref "H3") (pin "9") (pinfunction "9_9") (pintype "passive"))
      (node (ref "K1") (pin "1") (pinfunction "1_1") (pintype "passive"))
      (node (ref "K1") (pin "3") (pinfunction "3_3") (pintype "passive"))
      (node (ref "K1") (pin "5") (pinfunction "5_5") (pintype "passive"))
      (node (ref "K2") (pin "1") (pinfunction "1_1") (pintype "passive"))
      (node (ref "K2") (pin "3") (pinfunction "3_3") (pintype "passive"))
      (node (ref "K2") (pin "5") (pinfunction "5_5") (pintype "passive"))
      (node (ref "K2") (pin "7") (pinfunction "7_7") (pintype "passive"))
      (node (ref "K3") (pin "1") (pinfunction "1_1") (pintype "passive"))
      (node (ref "K3") (pin "3") (pinfunction "3_3") (pintype "passive"))
      (node (ref "K3") (pin "5") (pinfunction "5_5") (pintype "passive"))
      (node (ref "K4") (pin "1") (pinfunction "1_1") (pintype "passive"))
      (node (ref "K5") (pin "1") (pinfunction "1_1") (pintype "passive"))
      (node (ref "K5") (pin "3") (pinfunction "3_3") (pintype "passive"))
      (node (ref "K5") (pin "5") (pinfunction "5_5") (pintype "passive"))
      (node (ref "K5") (pin "7") (pinfunction "7_7") (pintype "passive"))
      (node (ref "LED1") (pin "K") (pinfunction "K_K") (pintype "passive"))
      (node (ref "LED10") (pin "K") (pinfunction "K_K") (pintype "passive"))
      (node (ref "LED11") (pin "K") (pinfunction "K_K") (pintype "passive"))
      (node (ref "LED12") (pin "K") (pinfunction "K_K") (pintype "passive"))
      (node (ref "LED13") (pin "K") (pinfunction "K_K") (pintype "passive"))
      (node (ref "LED14") (pin "K") (pinfunction "K_K") (pintype "passive"))
      (node (ref "LED15") (pin "K") (pinfunction "K_K") (pintype "passive"))
      (node (ref "LED16") (pin "K") (pinfunction "K_K") (pintype "passive"))
      (node (ref "LED2") (pin "K") (pinfunction "K_K") (pintype "passive"))
      (node (ref "LED3") (pin "K") (pinfunction "K_K") (pintype "passive"))
      (node (ref "LED4") (pin "K") (pinfunction "K_K") (pintype "passive"))
      (node (ref "LED5") (pin "K") (pinfunction "K_K") (pintype "passive"))
      (node (ref "LED6") (pin "K") (pinfunction "K_K") (pintype "passive"))
      (node (ref "LED7") (pin "K") (pinfunction "K_K") (pintype "passive"))
      (node (ref "LED8") (pin "K") (pinfunction "K_K") (pintype "passive"))
      (node (ref "LED9") (pin "K") (pinfunction "K_K") (pintype "passive"))
      (node (ref "P1") (pin "1") (pinfunction "1_1") (pintype "passive"))
      (node (ref "P10") (pin "21") (pinfunction "21_21") (pintype "passive"))
      (node (ref "P10") (pin "22") (pinfunction "22_22") (pintype "passive"))
      (node (ref "P10") (pin "31") (pinfunction "31_31") (pintype "passive"))
      (node (ref "P10") (pin "32") (pinfunction "32_32") (pintype "passive"))
      (node (ref "P10") (pin "7") (pinfunction "7_7") (pintype "passive"))
      (node (ref "P10") (pin "8") (pinfunction "8_8") (pintype "passive"))
      (node (ref "P2") (pin "1") (pinfunction "1_1") (pintype "passive"))
      (node (ref "P3") (pin "1") (pinfunction "1_1") (pintype "passive"))
      (node (ref "P4") (pin "1") (pinfunction "1_1") (pintype "passive"))
      (node (ref "P5") (pin "1") (pinfunction "1_1") (pintype "passive"))
      (node (ref "P6") (pin "1") (pinfunction "1_1") (pintype "passive"))
      (node (ref "P7") (pin "1") (pinfunction "1_1") (pintype "passive"))
      (node (ref "P8") (pin "1") (pinfunction "1_1") (pintype "passive"))
      (node (ref "P9") (pin "21") (pinfunction "21_21") (pintype "passive"))
      (node (ref "P9") (pin "22") (pinfunction "22_22") (pintype "passive"))
      (node (ref "P9") (pin "31") (pinfunction "31_31") (pintype "passive"))
      (node (ref "P9") (pin "32") (pinfunction "32_32") (pintype "passive"))
      (node (ref "P9") (pin "7") (pinfunction "7_7") (pintype "passive"))
      (node (ref "P9") (pin "8") (pinfunction "8_8") (pintype "passive"))
      (node (ref "R25") (pin "2") (pinfunction "2_2") (pintype "passive"))
      (node (ref "R26") (pin "2") (pinfunction "2_2") (pintype "passive"))
      (node (ref "R27") (pin "2") (pinfunction "2_2") (pintype "passive"))
      (node (ref "R28") (pin "2") (pinfunction "2_2") (pintype "passive"))
      (node (ref "TP16") (pin "1") (pinfunction "TP_1") (pintype "passive"))
      (node (ref "TP17") (pin "1") (pinfunction "TP_1") (pintype "passive"))
      (node (ref "TP18") (pin "1") (pinfunction "TP_1") (pintype "passive"))
      (node (ref "TP19") (pin "1") (pinfunction "TP_1") (pintype "passive"))
      (node (ref "TP20") (pin "1") (pinfunction "TP_1") (pintype "passive"))
    )
    (net (code "54") (name "unconnected-(H1-Pad1)") (class "Default")
      (node (ref "H1") (pin "1") (pinfunction "1_1") (pintype "passive+no_connect"))
    )
    (net (code "55") (name "unconnected-(H1-Pad2)") (class "Default")
      (node (ref "H1") (pin "2") (pinfunction "2_2") (pintype "passive+no_connect"))
    )
    (net (code "56") (name "unconnected-(H1-Pad3)") (class "Default")
      (node (ref "H1") (pin "3") (pinfunction "3_3") (pintype "passive+no_connect"))
    )
    (net (code "57") (name "unconnected-(H1-Pad4)") (class "Default")
      (node (ref "H1") (pin "4") (pinfunction "4_4") (pintype "passive+no_connect"))
    )
    (net (code "58") (name "unconnected-(H1-Pad5)") (class "Default")
      (node (ref "H1") (pin "5") (pinfunction "5_5") (pintype "passive+no_connect"))
    )
    (net (code "59") (name "unconnected-(H1-Pad6)") (class "Default")
      (node (ref "H1") (pin "6") (pinfunction "6_6") (pintype "passive+no_connect"))
    )
    (net (code "60") (name "unconnected-(H1-Pad7)") (class "Default")
      (node (ref "H1") (pin "7") (pinfunction "7_7") (pintype "passive+no_connect"))
    )
    (net (code "61") (name "unconnected-(H1-Pad8)") (class "Default")
      (node (ref "H1") (pin "8") (pinfunction "8_8") (pintype "passive+no_connect"))
    )
    (net (code "62") (name "unconnected-(H1-Pad9)") (class "Default")
      (node (ref "H1") (pin "9") (pinfunction "9_9") (pintype "passive+no_connect"))
    )
    (net (code "63") (name "unconnected-(H1-Pad10)") (class "Default")
      (node (ref "H1") (pin "10") (pinfunction "10_10") (pintype "passive+no_connect"))
    )
    (net (code "64") (name "unconnected-(H1-Pad11)") (class "Default")
      (node (ref "H1") (pin "11") (pinfunction "11_11") (pintype "passive+no_connect"))
    )
    (net (code "65") (name "unconnected-(H1-Pad12)") (class "Default")
      (node (ref "H1") (pin "12") (pinfunction "12_12") (pintype "passive+no_connect"))
    )
    (net (code "66") (name "unconnected-(H1-Pad14)") (class "Default")
      (node (ref "H1") (pin "14") (pinfunction "14_14") (pintype "passive+no_connect"))
    )
    (net (code "67") (name "unconnected-(H1-Pad16)") (class "Default")
      (node (ref "H1") (pin "16") (pinfunction "16_16") (pintype "passive+no_connect"))
    )
    (net (code "68") (name "unconnected-(H1-Pad18)") (class "Default")
      (node (ref "H1") (pin "18") (pinfunction "18_18") (pintype "passive+no_connect"))
    )
    (net (code "69") (name "unconnected-(H1-Pad19)") (class "Default")
      (node (ref "H1") (pin "19") (pinfunction "19_19") (pintype "passive+no_connect"))
    )
    (net (code "70") (name "unconnected-(H1-Pad20)") (class "Default")
      (node (ref "H1") (pin "20") (pinfunction "20_20") (pintype "passive+no_connect"))
    )
    (net (code "71") (name "unconnected-(H1-Pad22)") (class "Default")
      (node (ref "H1") (pin "22") (pinfunction "22_22") (pintype "passive+no_connect"))
    )
    (net (code "72") (name "unconnected-(H1-Pad24)") (class "Default")
      (node (ref "H1") (pin "24") (pinfunction "24_24") (pintype "passive+no_connect"))
    )
    (net (code "73") (name "unconnected-(H1-Pad25)") (class "Default")
      (node (ref "H1") (pin "25") (pinfunction "25_25") (pintype "passive+no_connect"))
    )
    (net (code "74") (name "unconnected-(H1-Pad26)") (class "Default")
      (node (ref "H1") (pin "26") (pinfunction "26_26") (pintype "passive+no_connect"))
    )
    (net (code "75") (name "unconnected-(H1-Pad27)") (class "Default")
      (node (ref "H1") (pin "27") (pinfunction "27_27") (pintype "passive+no_connect"))
    )
    (net (code "76") (name "unconnected-(H1-Pad28)") (class "Default")
      (node (ref "H1") (pin "28") (pinfunction "28_28") (pintype "passive+no_connect"))
    )
    (net (code "77") (name "unconnected-(H1-Pad29)") (class "Default")
      (node (ref "H1") (pin "29") (pinfunction "29_29") (pintype "passive+no_connect"))
    )
    (net (code "78") (name "unconnected-(H1-Pad30)") (class "Default")
      (node (ref "H1") (pin "30") (pinfunction "30_30") (pintype "passive+no_connect"))
    )
    (net (code "79") (name "unconnected-(H1-Pad31)") (class "Default")
      (node (ref "H1") (pin "31") (pinfunction "31_31") (pintype "passive+no_connect"))
    )
    (net (code "80") (name "unconnected-(H1-Pad32)") (class "Default")
      (node (ref "H1") (pin "32") (pinfunction "32_32") (pintype "passive+no_connect"))
    )
    (net (code "81") (name "unconnected-(H1-Pad36)") (class "Default")
      (node (ref "H1") (pin "36") (pinfunction "36_36") (pintype "passive"))
    )
    (net (code "82") (name "unconnected-(H1-Pad42)") (class "Default")
      (node (ref "H1") (pin "42") (pinfunction "42_42") (pintype "passive+no_connect"))
    )
    (net (code "83") (name "unconnected-(H1-Pad44)") (class "Default")
      (node (ref "H1") (pin "44") (pinfunction "44_44") (pintype "passive+no_connect"))
    )
    (net (code "84") (name "unconnected-(H1-Pad45)") (class "Default")
      (node (ref "H1") (pin "45") (pinfunction "45_45") (pintype "passive+no_connect"))
    )
    (net (code "85") (name "unconnected-(H1-Pad46)") (class "Default")
      (node (ref "H1") (pin "46") (pinfunction "46_46") (pintype "passive+no_connect"))
    )
    (net (code "86") (name "unconnected-(H1-Pad47)") (class "Default")
      (node (ref "H1") (pin "47") (pinfunction "47_47") (pintype "passive+no_connect"))
    )
    (net (code "87") (name "unconnected-(H1-Pad49)") (class "Default")
      (node (ref "H1") (pin "49") (pinfunction "49_49") (pintype "passive+no_connect"))
    )
    (net (code "88") (name "unconnected-(H1-Pad51)") (class "Default")
      (node (ref "H1") (pin "51") (pinfunction "51_51") (pintype "passive+no_connect"))
    )
    (net (code "89") (name "unconnected-(H2-Pad1)") (class "Default")
      (node (ref "H2") (pin "1") (pinfunction "1_1") (pintype "passive+no_connect"))
    )
    (net (code "90") (name "unconnected-(H2-Pad2)") (class "Default")
      (node (ref "H2") (pin "2") (pinfunction "2_2") (pintype "passive+no_connect"))
    )
    (net (code "91") (name "unconnected-(H2-Pad3)") (class "Default")
      (node (ref "H2") (pin "3") (pinfunction "3_3") (pintype "passive+no_connect"))
    )
    (net (code "92") (name "unconnected-(H2-Pad4)") (class "Default")
      (node (ref "H2") (pin "4") (pinfunction "4_4") (pintype "passive+no_connect"))
    )
    (net (code "93") (name "unconnected-(H2-Pad5)") (class "Default")
      (node (ref "H2") (pin "5") (pinfunction "5_5") (pintype "passive+no_connect"))
    )
    (net (code "94") (name "unconnected-(H2-Pad6)") (class "Default")
      (node (ref "H2") (pin "6") (pinfunction "6_6") (pintype "passive+no_connect"))
    )
    (net (code "95") (name "unconnected-(H2-Pad7)") (class "Default")
      (node (ref "H2") (pin "7") (pinfunction "7_7") (pintype "passive+no_connect"))
    )
    (net (code "96") (name "unconnected-(H2-Pad8)") (class "Default")
      (node (ref "H2") (pin "8") (pinfunction "8_8") (pintype "passive+no_connect"))
    )
    (net (code "97") (name "unconnected-(H2-Pad9)") (class "Default")
      (node (ref "H2") (pin "9") (pinfunction "9_9") (pintype "passive+no_connect"))
    )
    (net (code "98") (name "unconnected-(H2-Pad10)") (class "Default")
      (node (ref "H2") (pin "10") (pinfunction "10_10") (pintype "passive+no_connect"))
    )
    (net (code "99") (name "unconnected-(H2-Pad11)") (class "Default")
      (node (ref "H2") (pin "11") (pinfunction "11_11") (pintype "passive+no_connect"))
    )
    (net (code "100") (name "unconnected-(H2-Pad12)") (class "Default")
      (node (ref "H2") (pin "12") (pinfunction "12_12") (pintype "passive+no_connect"))
    )
    (net (code "101") (name "unconnected-(H2-Pad13)") (class "Default")
      (node (ref "H2") (pin "13") (pinfunction "13_13") (pintype "passive+no_connect"))
    )
    (net (code "102") (name "unconnected-(H2-Pad14)") (class "Default")
      (node (ref "H2") (pin "14") (pinfunction "14_14") (pintype "passive+no_connect"))
    )
    (net (code "103") (name "unconnected-(H2-Pad15)") (class "Default")
      (node (ref "H2") (pin "15") (pinfunction "15_15") (pintype "passive+no_connect"))
    )
    (net (code "104") (name "unconnected-(H2-Pad16)") (class "Default")
      (node (ref "H2") (pin "16") (pinfunction "16_16") (pintype "passive+no_connect"))
    )
    (net (code "105") (name "unconnected-(H2-Pad17)") (class "Default")
      (node (ref "H2") (pin "17") (pinfunction "17_17") (pintype "passive+no_connect"))
    )
    (net (code "106") (name "unconnected-(H2-Pad18)") (class "Default")
      (node (ref "H2") (pin "18") (pinfunction "18_18") (pintype "passive+no_connect"))
    )
    (net (code "107") (name "unconnected-(H2-Pad19)") (class "Default")
      (node (ref "H2") (pin "19") (pinfunction "19_19") (pintype "passive+no_connect"))
    )
    (net (code "108") (name "unconnected-(H2-Pad20)") (class "Default")
      (node (ref "H2") (pin "20") (pinfunction "20_20") (pintype "passive+no_connect"))
    )
    (net (code "109") (name "unconnected-(H2-Pad21)") (class "Default")
      (node (ref "H2") (pin "21") (pinfunction "21_21") (pintype "passive+no_connect"))
    )
    (net (code "110") (name "unconnected-(H2-Pad22)") (class "Default")
      (node (ref "H2") (pin "22") (pinfunction "22_22") (pintype "passive+no_connect"))
    )
    (net (code "111") (name "unconnected-(H2-Pad23)") (class "Default")
      (node (ref "H2") (pin "23") (pinfunction "23_23") (pintype "passive+no_connect"))
    )
    (net (code "112") (name "unconnected-(H2-Pad24)") (class "Default")
      (node (ref "H2") (pin "24") (pinfunction "24_24") (pintype "passive+no_connect"))
    )
    (net (code "113") (name "unconnected-(H2-Pad33)") (class "Default")
      (node (ref "H2") (pin "33") (pinfunction "33_33") (pintype "passive+no_connect"))
    )
    (net (code "114") (name "unconnected-(H2-Pad34)") (class "Default")
      (node (ref "H2") (pin "34") (pinfunction "34_34") (pintype "passive+no_connect"))
    )
    (net (code "115") (name "unconnected-(H2-Pad36)") (class "Default")
      (node (ref "H2") (pin "36") (pinfunction "36_36") (pintype "passive+no_connect"))
    )
    (net (code "116") (name "unconnected-(H2-Pad38)") (class "Default")
      (node (ref "H2") (pin "38") (pinfunction "38_38") (pintype "passive+no_connect"))
    )
    (net (code "117") (name "unconnected-(H2-Pad40)") (class "Default")
      (node (ref "H2") (pin "40") (pinfunction "40_40") (pintype "passive+no_connect"))
    )
    (net (code "118") (name "unconnected-(H2-Pad41)") (class "Default")
      (node (ref "H2") (pin "41") (pinfunction "41_41") (pintype "passive+no_connect"))
    )
    (net (code "119") (name "unconnected-(H2-Pad42)") (class "Default")
      (node (ref "H2") (pin "42") (pinfunction "42_42") (pintype "passive+no_connect"))
    )
    (net (code "120") (name "unconnected-(H2-Pad43)") (class "Default")
      (node (ref "H2") (pin "43") (pinfunction "43_43") (pintype "passive+no_connect"))
    )
    (net (code "121") (name "unconnected-(H2-Pad44)") (class "Default")
      (node (ref "H2") (pin "44") (pinfunction "44_44") (pintype "passive+no_connect"))
    )
    (net (code "122") (name "unconnected-(H2-Pad47)") (class "Default")
      (node (ref "H2") (pin "47") (pinfunction "47_47") (pintype "passive+no_connect"))
    )
    (net (code "123") (name "unconnected-(H2-Pad48)") (class "Default")
      (node (ref "H2") (pin "48") (pinfunction "48_48") (pintype "passive+no_connect"))
    )
    (net (code "124") (name "unconnected-(H2-Pad49)") (class "Default")
      (node (ref "H2") (pin "49") (pinfunction "49_49") (pintype "passive+no_connect"))
    )
    (net (code "125") (name "unconnected-(H2-Pad50)") (class "Default")
      (node (ref "H2") (pin "50") (pinfunction "50_50") (pintype "passive+no_connect"))
    )
    (net (code "126") (name "unconnected-(H2-Pad51)") (class "Default")
      (node (ref "H2") (pin "51") (pinfunction "51_51") (pintype "passive+no_connect"))
    )
    (net (code "127") (name "unconnected-(H2-Pad52)") (class "Default")
      (node (ref "H2") (pin "52") (pinfunction "52_52") (pintype "passive+no_connect"))
    )
  )
)
